# controller.net
KiCad netlist of a schematic drawn in EAGLE
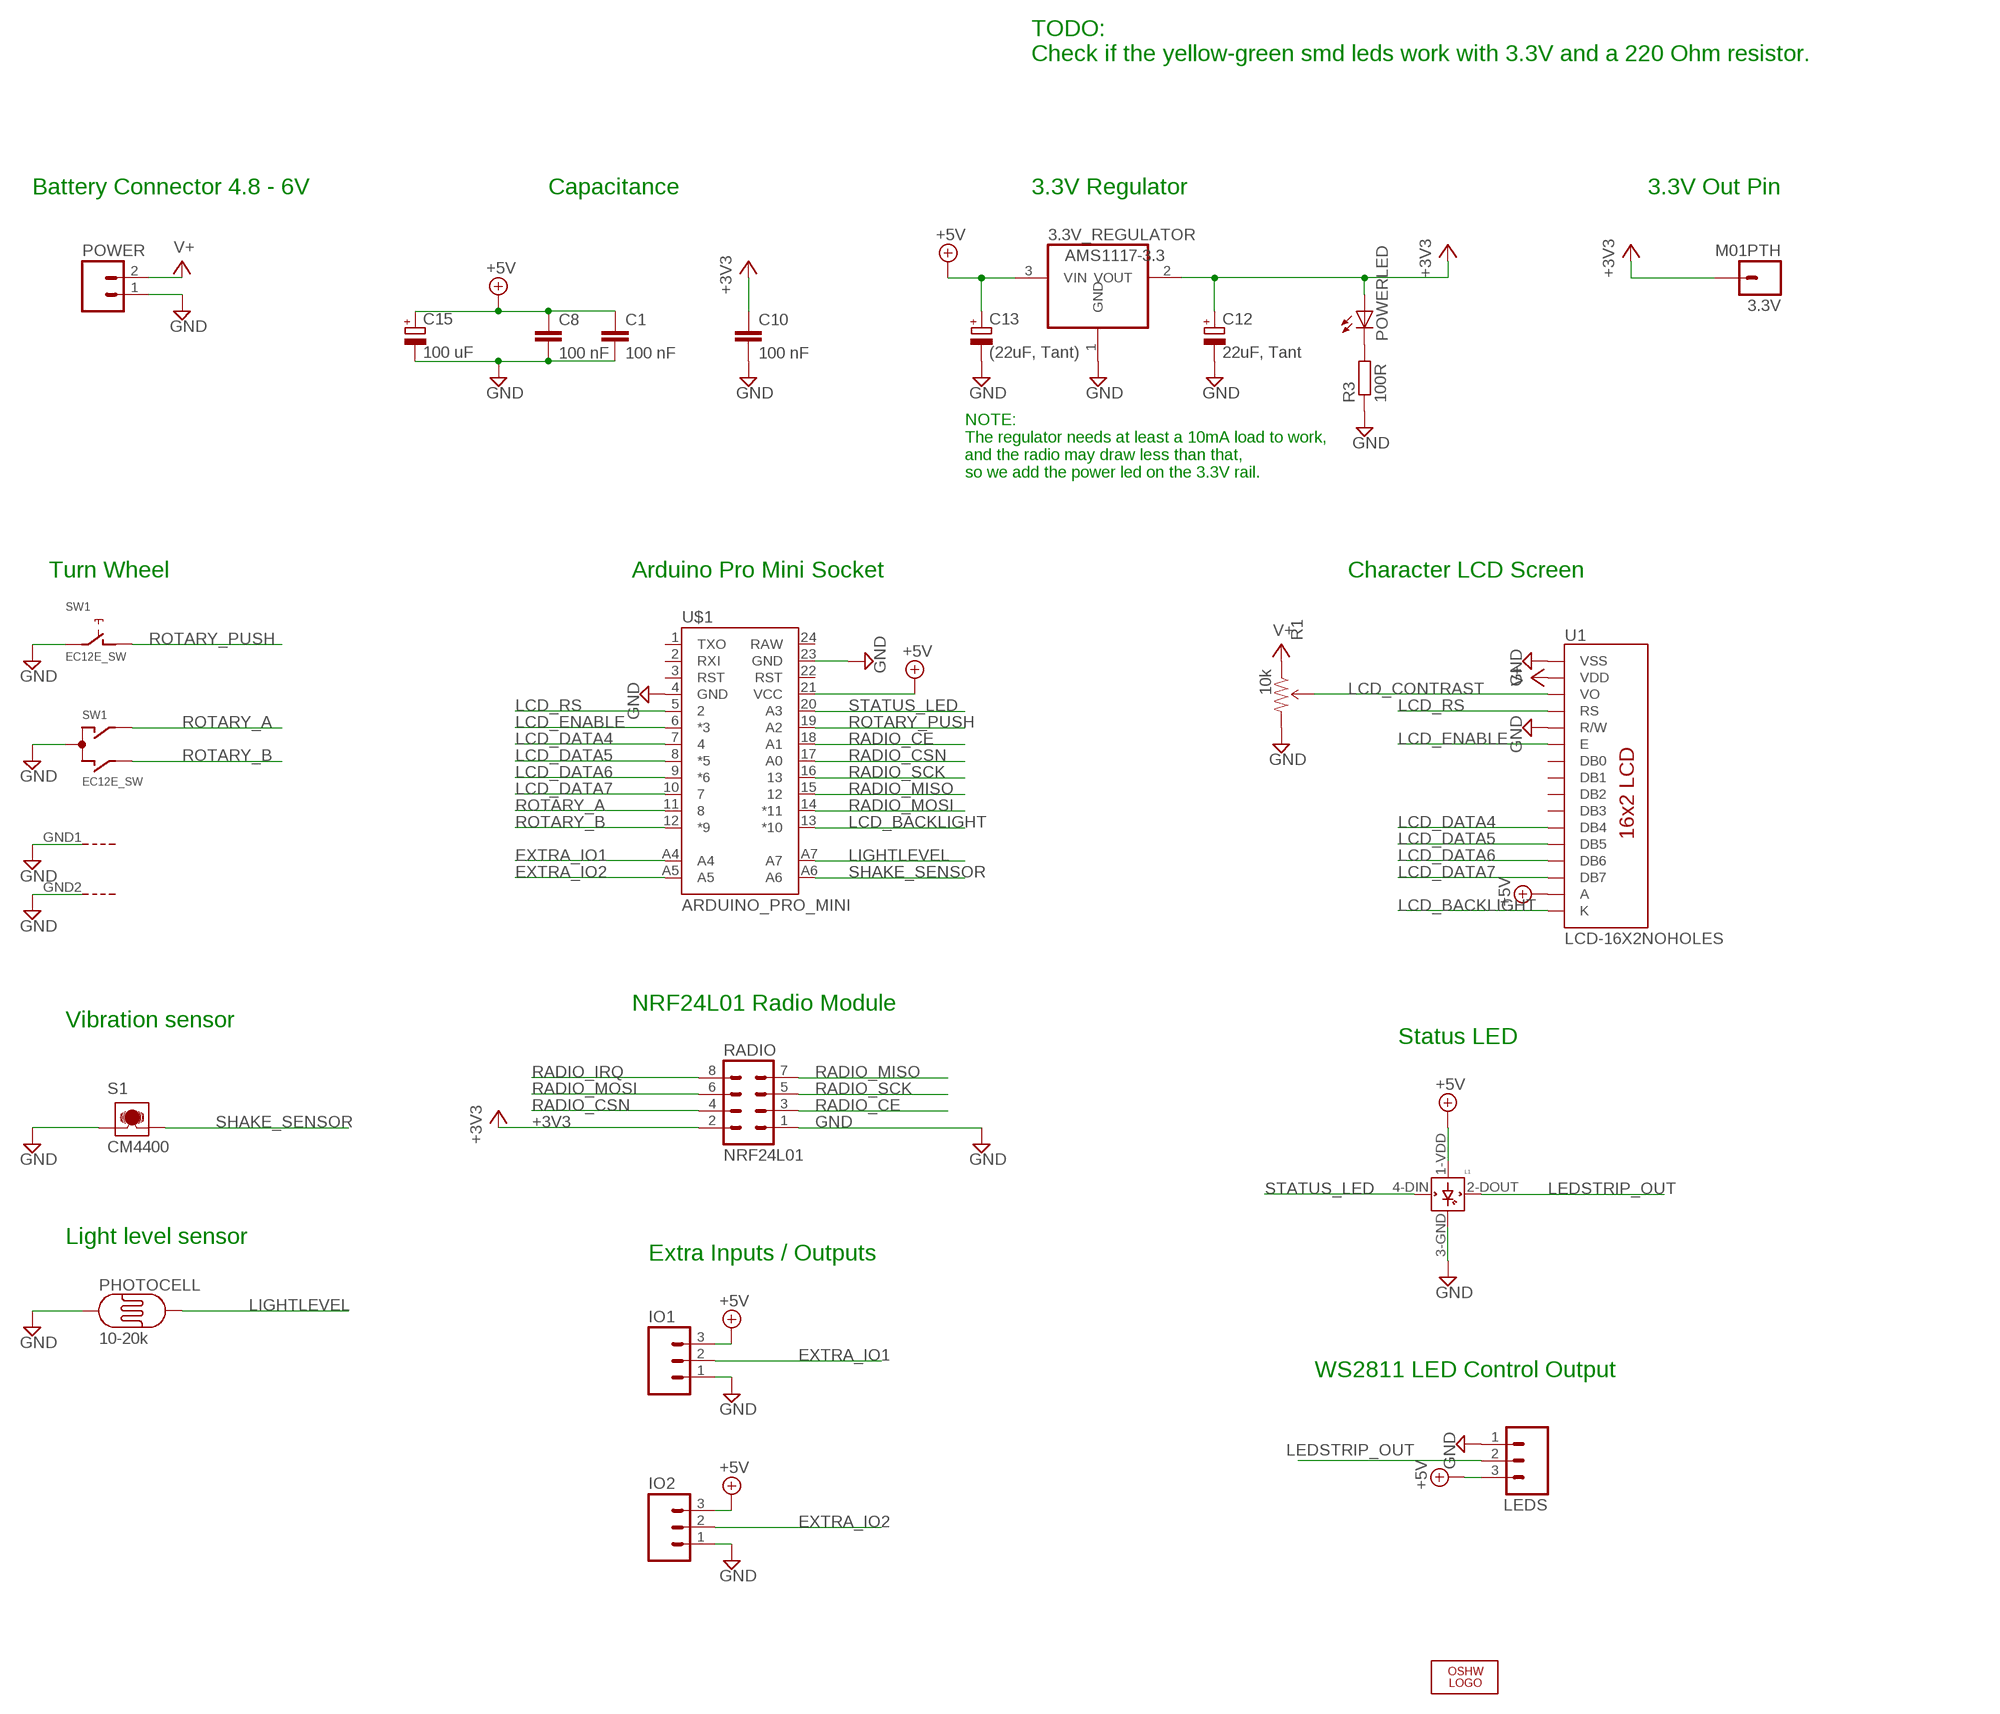
[diagram p0: schematic, sheet 1]

(export (version "E")
  (design (tool "Eeschema 10.0.6"))
  (components
    (comp (ref "3.3V")
      (value "M01PTH")
      (footprint "eagle-import:1X01")
      (libsource (lib "eagle-import") (part "M01PTH"))
    )
    (comp (ref "3.3V_REGULATOR")
      (value "AMS1117-3.3")
      (footprint "eagle-import:SOT223")
      (fields (field (name "MPN") "REG1117"))
      (libsource (lib "eagle-import") (part "REG1117"))
    )
    (comp (ref "C1")
      (value "100 nF")
      (footprint "eagle-import:C0805")
      (libsource (lib "eagle-import") (part "C-EUC0805"))
    )
    (comp (ref "C8")
      (value "100 nF")
      (footprint "eagle-import:C0805")
      (libsource (lib "eagle-import") (part "C-EUC0805"))
    )
    (comp (ref "C10")
      (value "100 nF")
      (footprint "eagle-import:C0805")
      (libsource (lib "eagle-import") (part "C-EUC0805"))
    )
    (comp (ref "C12")
      (value "22uF, Tant")
      (footprint "eagle-import:SMC_A")
      (libsource (lib "eagle-import") (part "CPOL-EUSMCA"))
    )
    (comp (ref "C13")
      (value "(22uF, Tant)")
      (footprint "eagle-import:SMC_A")
      (libsource (lib "eagle-import") (part "CPOL-EUSMCA"))
    )
    (comp (ref "C15")
      (value "100 uF")
      (footprint "eagle-import:E2,5-6")
      (libsource (lib "eagle-import") (part "CPOL-EUE2.5-6"))
    )
    (comp (ref "IO1")
      (value "M03PTH")
      (footprint "eagle-import:1X03")
      (libsource (lib "eagle-import") (part "M03PTH"))
    )
    (comp (ref "IO2")
      (value "M03PTH")
      (footprint "eagle-import:1X03")
      (libsource (lib "eagle-import") (part "M03PTH"))
    )
    (comp (ref "L1")
      (value "WS2812B")
      (footprint "eagle-import:WS2812B")
      (libsource (lib "eagle-import") (part "WS2812B"))
    )
    (comp (ref "LEDS")
      (value "M03PTH")
      (footprint "eagle-import:1X03")
      (libsource (lib "eagle-import") (part "M03PTH"))
    )
    (comp (ref "LOGO3")
      (value "LOGO-OSHW-8MILX0100-NT")
      (footprint "eagle-import:OSHW_8X100_NOTEXT")
      (libsource (lib "eagle-import") (part "LOGO-OSHW-8MILX0100-NT"))
    )
    (comp (ref "PHOTOCELL")
      (value "10-20k")
      (footprint "eagle-import:PHOTOCELL")
      (libsource (lib "eagle-import") (part "PHOTOCELLPTH"))
    )
    (comp (ref "POWER")
      (value "M02LOCK_LONGPADS")
      (footprint "eagle-import:1X02_LOCK_LONGPADS")
      (libsource (lib "eagle-import") (part "M02LOCK_LONGPADS"))
    )
    (comp (ref "POWERLED")
      (value "LEDSMT1206")
      (footprint "eagle-import:1206")
      (libsource (lib "eagle-import") (part "LEDSMT1206"))
    )
    (comp (ref "R1")
      (value "10k")
      (footprint "eagle-import:3362U-2")
      (libsource (lib "eagle-import") (part "TRIMPOT"))
    )
    (comp (ref "R3")
      (value "100R")
      (footprint "eagle-import:M0805")
      (libsource (lib "eagle-import") (part "R-EU_M0805"))
    )
    (comp (ref "RADIO")
      (value "NRF24L01")
      (footprint "eagle-import:MA04-2")
      (libsource (lib "eagle-import") (part "MA04-2"))
    )
    (comp (ref "S1")
      (value "CM4400")
      (footprint "eagle-import:CM4400")
      (fields (field (name "MF") "FARNELL") (field (name "MPN") "CM4400-1."))
      (libsource (lib "eagle-import") (part "CM4400"))
    )
    (comp (ref "SW1")
      (value "EC12E_SW")
      (footprint "eagle-import:ALPS_EC12E_SW")
      (fields (field (name "MPN") "EC12E2424407"))
      (libsource (lib "eagle-import") (part "EC12E_SW"))
    )
    (comp (ref "U$1")
      (value "ARDUINO_PRO_MINI")
      (footprint "eagle-import:ARDUINO_PRO_MINI")
      (libsource (lib "eagle-import") (part "ARDUINO_PRO_MINI"))
    )
    (comp (ref "U1")
      (value "LCD-16X2NOHOLES")
      (footprint "eagle-import:LCD-16X2_NOHOLES")
      (libsource (lib "eagle-import") (part "LCD-16X2NOHOLES"))
    )
  )
  (nets
    (net (code "1") (name "+3V3") (class "Default")
      (node (ref "3.3V") (pin "1") (pinfunction "1_1") (pintype "passive"))
      (node (ref "3.3V_REGULATOR") (pin "2") (pinfunction "VOUT_2") (pintype "output"))
      (node (ref "C10") (pin "1") (pinfunction "1_1") (pintype "passive"))
      (node (ref "C12") (pin "+") (pinfunction "+_+") (pintype "passive"))
      (node (ref "POWERLED") (pin "A") (pinfunction "A_A") (pintype "passive"))
      (node (ref "RADIO") (pin "2") (pinfunction "2_2") (pintype "passive"))
    )
    (net (code "2") (name "+5V") (class "Default")
      (node (ref "3.3V_REGULATOR") (pin "3") (pinfunction "VIN_3") (pintype "input"))
      (node (ref "C1") (pin "1") (pinfunction "1_1") (pintype "passive"))
      (node (ref "C13") (pin "+") (pinfunction "+_+") (pintype "passive"))
      (node (ref "C15") (pin "+") (pinfunction "+_+") (pintype "passive"))
      (node (ref "C8") (pin "1") (pinfunction "1_1") (pintype "passive"))
      (node (ref "IO1") (pin "3") (pinfunction "3_3") (pintype "passive"))
      (node (ref "IO2") (pin "3") (pinfunction "3_3") (pintype "passive"))
      (node (ref "L1") (pin "1-VDD") (pinfunction "VDD_1-VDD") (pintype "bidirectional"))
      (node (ref "LEDS") (pin "3") (pinfunction "3_3") (pintype "passive"))
      (node (ref "U$1") (pin "21") (pinfunction "VCC_21") (pintype "bidirectional"))
      (node (ref "U1") (pin "15") (pinfunction "A_15") (pintype "power_in"))
    )
    (net (code "3") (name "/EXTRA_IO1") (class "Default")
      (node (ref "IO1") (pin "2") (pinfunction "2_2") (pintype "passive"))
      (node (ref "U$1") (pin "A4") (pinfunction "A4_A4") (pintype "bidirectional"))
    )
    (net (code "4") (name "/EXTRA_IO2") (class "Default")
      (node (ref "IO2") (pin "2") (pinfunction "2_2") (pintype "passive"))
      (node (ref "U$1") (pin "A5") (pinfunction "A5_A5") (pintype "bidirectional"))
    )
    (net (code "5") (name "/LCD_BACKLIGHT") (class "Default")
      (node (ref "U$1") (pin "13") (pinfunction "*10_13") (pintype "bidirectional"))
      (node (ref "U1") (pin "16") (pinfunction "K_16") (pintype "power_in"))
    )
    (net (code "6") (name "/LCD_CONTRAST") (class "Default")
      (node (ref "R1") (pin "2") (pinfunction "WIPER_2") (pintype "passive"))
      (node (ref "U1") (pin "3") (pinfunction "VO_3") (pintype "bidirectional"))
    )
    (net (code "7") (name "/LCD_DATA4") (class "Default")
      (node (ref "U$1") (pin "7") (pinfunction "4_7") (pintype "bidirectional"))
      (node (ref "U1") (pin "11") (pinfunction "DB4_11") (pintype "bidirectional"))
    )
    (net (code "8") (name "/LCD_DATA5") (class "Default")
      (node (ref "U$1") (pin "8") (pinfunction "*5_8") (pintype "bidirectional"))
      (node (ref "U1") (pin "12") (pinfunction "DB5_12") (pintype "bidirectional"))
    )
    (net (code "9") (name "/LCD_DATA6") (class "Default")
      (node (ref "U$1") (pin "9") (pinfunction "*6_9") (pintype "bidirectional"))
      (node (ref "U1") (pin "13") (pinfunction "DB6_13") (pintype "bidirectional"))
    )
    (net (code "10") (name "/LCD_DATA7") (class "Default")
      (node (ref "U$1") (pin "10") (pinfunction "7_10") (pintype "bidirectional"))
      (node (ref "U1") (pin "14") (pinfunction "DB7_14") (pintype "bidirectional"))
    )
    (net (code "11") (name "/LCD_ENABLE") (class "Default")
      (node (ref "U$1") (pin "6") (pinfunction "*3_6") (pintype "bidirectional"))
      (node (ref "U1") (pin "6") (pinfunction "E_6") (pintype "input"))
    )
    (net (code "12") (name "/LCD_RS") (class "Default")
      (node (ref "U$1") (pin "5") (pinfunction "2_5") (pintype "bidirectional"))
      (node (ref "U1") (pin "4") (pinfunction "RS_4") (pintype "input"))
    )
    (net (code "13") (name "/LEDSTRIP_OUT") (class "Default")
      (node (ref "L1") (pin "2-DOUT") (pinfunction "DOUT_2-DOUT") (pintype "output"))
      (node (ref "LEDS") (pin "2") (pinfunction "2_2") (pintype "passive"))
    )
    (net (code "14") (name "/LIGHTLEVEL") (class "Default")
      (node (ref "PHOTOCELL") (pin "2") (pinfunction "P$2_2") (pintype "bidirectional"))
      (node (ref "U$1") (pin "A7") (pinfunction "A7_A7") (pintype "bidirectional"))
    )
    (net (code "15") (name "/RADIO_CE") (class "Default")
      (node (ref "RADIO") (pin "3") (pinfunction "3_3") (pintype "passive"))
      (node (ref "U$1") (pin "18") (pinfunction "A1_18") (pintype "bidirectional"))
    )
    (net (code "16") (name "/RADIO_CSN") (class "Default")
      (node (ref "RADIO") (pin "4") (pinfunction "4_4") (pintype "passive"))
      (node (ref "U$1") (pin "17") (pinfunction "A0_17") (pintype "bidirectional"))
    )
    (net (code "17") (name "/RADIO_IRQ") (class "Default")
      (node (ref "RADIO") (pin "8") (pinfunction "8_8") (pintype "passive"))
    )
    (net (code "18") (name "/RADIO_MISO") (class "Default")
      (node (ref "RADIO") (pin "7") (pinfunction "7_7") (pintype "passive"))
      (node (ref "U$1") (pin "15") (pinfunction "12_15") (pintype "bidirectional"))
    )
    (net (code "19") (name "/RADIO_MOSI") (class "Default")
      (node (ref "RADIO") (pin "6") (pinfunction "6_6") (pintype "passive"))
      (node (ref "U$1") (pin "14") (pinfunction "*11_14") (pintype "bidirectional"))
    )
    (net (code "20") (name "/RADIO_SCK") (class "Default")
      (node (ref "RADIO") (pin "5") (pinfunction "5_5") (pintype "passive"))
      (node (ref "U$1") (pin "16") (pinfunction "13_16") (pintype "bidirectional"))
    )
    (net (code "21") (name "/ROTARY_A") (class "Default")
      (node (ref "SW1") (pin "A") (pinfunction "A_A") (pintype "passive"))
      (node (ref "U$1") (pin "11") (pinfunction "8_11") (pintype "bidirectional"))
    )
    (net (code "22") (name "/ROTARY_B") (class "Default")
      (node (ref "SW1") (pin "B") (pinfunction "B_B") (pintype "passive"))
      (node (ref "U$1") (pin "12") (pinfunction "*9_12") (pintype "bidirectional"))
    )
    (net (code "23") (name "/ROTARY_PUSH") (class "Default")
      (node (ref "SW1") (pin "D") (pinfunction "1_D") (pintype "passive"))
      (node (ref "U$1") (pin "19") (pinfunction "A2_19") (pintype "bidirectional"))
    )
    (net (code "24") (name "/SHAKE_SENSOR") (class "Default")
      (node (ref "S1") (pin "2") (pinfunction "2_2") (pintype "passive"))
      (node (ref "U$1") (pin "A6") (pinfunction "A6_A6") (pintype "bidirectional"))
    )
    (net (code "25") (name "/STATUS_LED") (class "Default")
      (node (ref "L1") (pin "4-DIN") (pinfunction "DIN_4-DIN") (pintype "input"))
      (node (ref "U$1") (pin "20") (pinfunction "A3_20") (pintype "bidirectional"))
    )
    (net (code "26") (name "GND") (class "Default")
      (node (ref "3.3V_REGULATOR") (pin "1") (pinfunction "GND_1") (pintype "power_in"))
      (node (ref "C1") (pin "2") (pinfunction "2_2") (pintype "passive"))
      (node (ref "C10") (pin "2") (pinfunction "2_2") (pintype "passive"))
      (node (ref "C12") (pin "-") (pinfunction "-_-") (pintype "passive"))
      (node (ref "C13") (pin "-") (pinfunction "-_-") (pintype "passive"))
      (node (ref "C15") (pin "-") (pinfunction "-_-") (pintype "passive"))
      (node (ref "C8") (pin "2") (pinfunction "2_2") (pintype "passive"))
      (node (ref "IO1") (pin "1") (pinfunction "1_1") (pintype "passive"))
      (node (ref "IO2") (pin "1") (pinfunction "1_1") (pintype "passive"))
      (node (ref "L1") (pin "3-GND") (pinfunction "GND_3-GND") (pintype "bidirectional"))
      (node (ref "LEDS") (pin "1") (pinfunction "1_1") (pintype "passive"))
      (node (ref "PHOTOCELL") (pin "1") (pinfunction "P$1_1") (pintype "bidirectional"))
      (node (ref "POWER") (pin "1") (pinfunction "1_1") (pintype "passive"))
      (node (ref "R1") (pin "3") (pinfunction "CW_3") (pintype "passive"))
      (node (ref "R3") (pin "1") (pinfunction "1_1") (pintype "passive"))
      (node (ref "RADIO") (pin "1") (pinfunction "1_1") (pintype "passive"))
      (node (ref "S1") (pin "1") (pinfunction "1_1") (pintype "passive"))
      (node (ref "SW1") (pin "C") (pinfunction "C_C") (pintype "passive"))
      (node (ref "SW1") (pin "E") (pinfunction "2_E") (pintype "passive"))
      (node (ref "SW1") (pin "GND1") (pinfunction "G_GND1") (pintype "passive"))
      (node (ref "SW1") (pin "GND2") (pinfunction "G_GND2") (pintype "passive"))
      (node (ref "U$1") (pin "23") (pinfunction "GND_23") (pintype "bidirectional"))
      (node (ref "U$1") (pin "4") (pinfunction "GND_4") (pintype "bidirectional"))
      (node (ref "U1") (pin "1") (pinfunction "VSS_1") (pintype "power_in"))
      (node (ref "U1") (pin "5") (pinfunction "R/W_5") (pintype "input"))
    )
    (net (code "27") (name "Net-(POWERLED-PadC)") (class "Default")
      (node (ref "POWERLED") (pin "C") (pinfunction "C_C") (pintype "passive"))
      (node (ref "R3") (pin "2") (pinfunction "2_2") (pintype "passive"))
    )
    (net (code "28") (name "V+") (class "Default")
      (node (ref "POWER") (pin "2") (pinfunction "2_2") (pintype "passive"))
      (node (ref "R1") (pin "1") (pinfunction "CCW_1") (pintype "passive"))
      (node (ref "U1") (pin "2") (pinfunction "VDD_2") (pintype "power_in"))
    )
    (net (code "29") (name "unconnected-(U$1-RAW-Pad24)") (class "Default")
      (node (ref "U$1") (pin "24") (pinfunction "RAW_24") (pintype "bidirectional"))
    )
    (net (code "30") (name "unconnected-(U$1-RST-Pad3)") (class "Default")
      (node (ref "U$1") (pin "3") (pinfunction "RST_3") (pintype "bidirectional"))
    )
    (net (code "31") (name "unconnected-(U$1-RST-Pad22)") (class "Default")
      (node (ref "U$1") (pin "22") (pinfunction "RST_22") (pintype "bidirectional"))
    )
    (net (code "32") (name "unconnected-(U$1-RXI-Pad2)") (class "Default")
      (node (ref "U$1") (pin "2") (pinfunction "RXI_2") (pintype "bidirectional"))
    )
    (net (code "33") (name "unconnected-(U$1-TXO-Pad1)") (class "Default")
      (node (ref "U$1") (pin "1") (pinfunction "TXO_1") (pintype "bidirectional"))
    )
    (net (code "34") (name "unconnected-(U1-DB0-Pad7)") (class "Default")
      (node (ref "U1") (pin "7") (pinfunction "DB0_7") (pintype "bidirectional"))
    )
    (net (code "35") (name "unconnected-(U1-DB1-Pad8)") (class "Default")
      (node (ref "U1") (pin "8") (pinfunction "DB1_8") (pintype "bidirectional"))
    )
    (net (code "36") (name "unconnected-(U1-DB2-Pad9)") (class "Default")
      (node (ref "U1") (pin "9") (pinfunction "DB2_9") (pintype "bidirectional"))
    )
    (net (code "37") (name "unconnected-(U1-DB3-Pad10)") (class "Default")
      (node (ref "U1") (pin "10") (pinfunction "DB3_10") (pintype "bidirectional"))
    )
  )
)
